# EMG_CHANNEL_2_ANALOG.net
KiCad netlist of a schematic drawn in Altium Designer
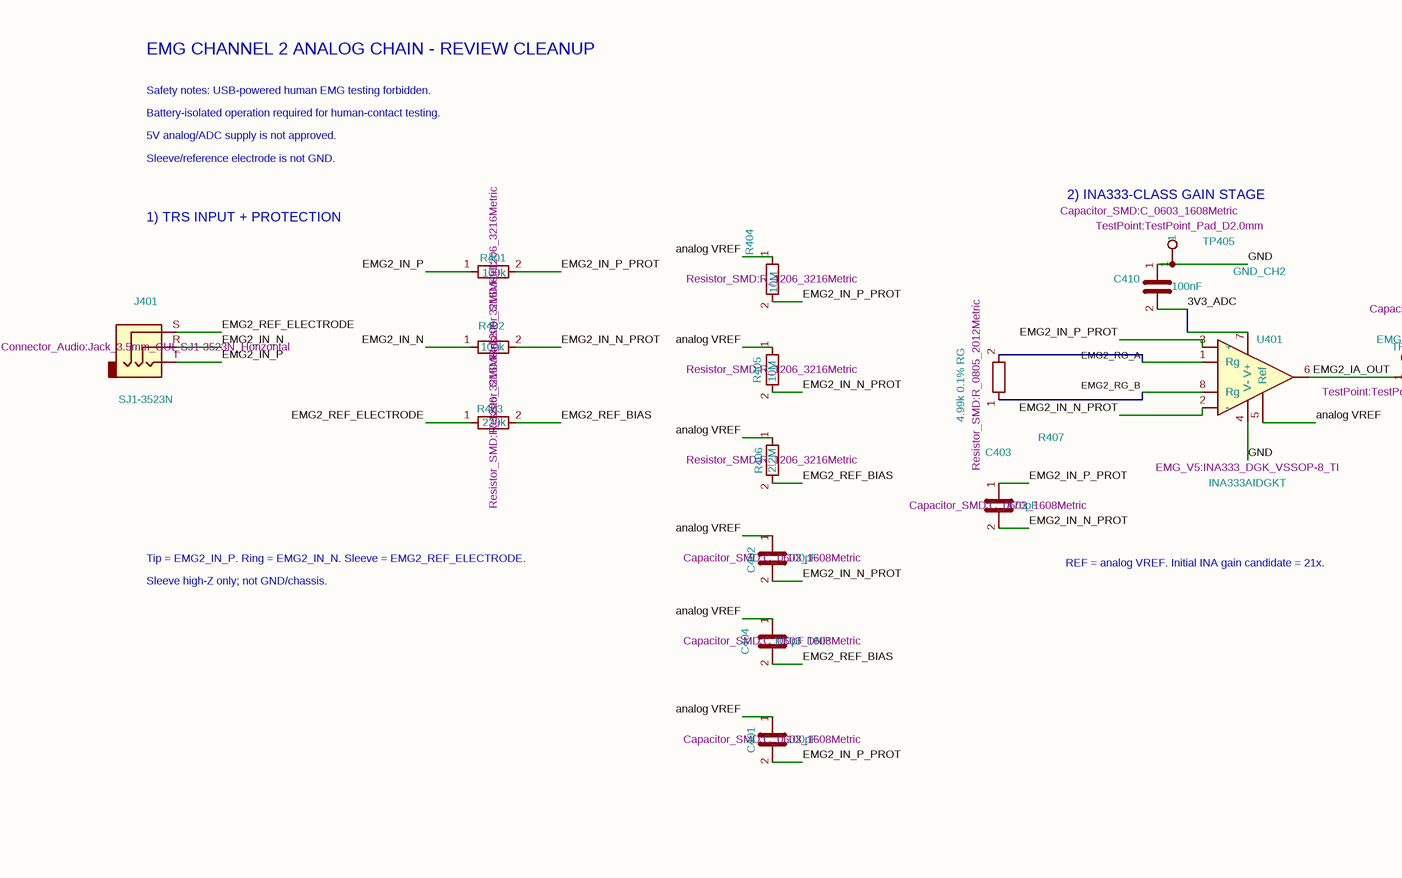
[diagram p0: EMG_CHANNEL_2_ANALOG.SchDoc, left]
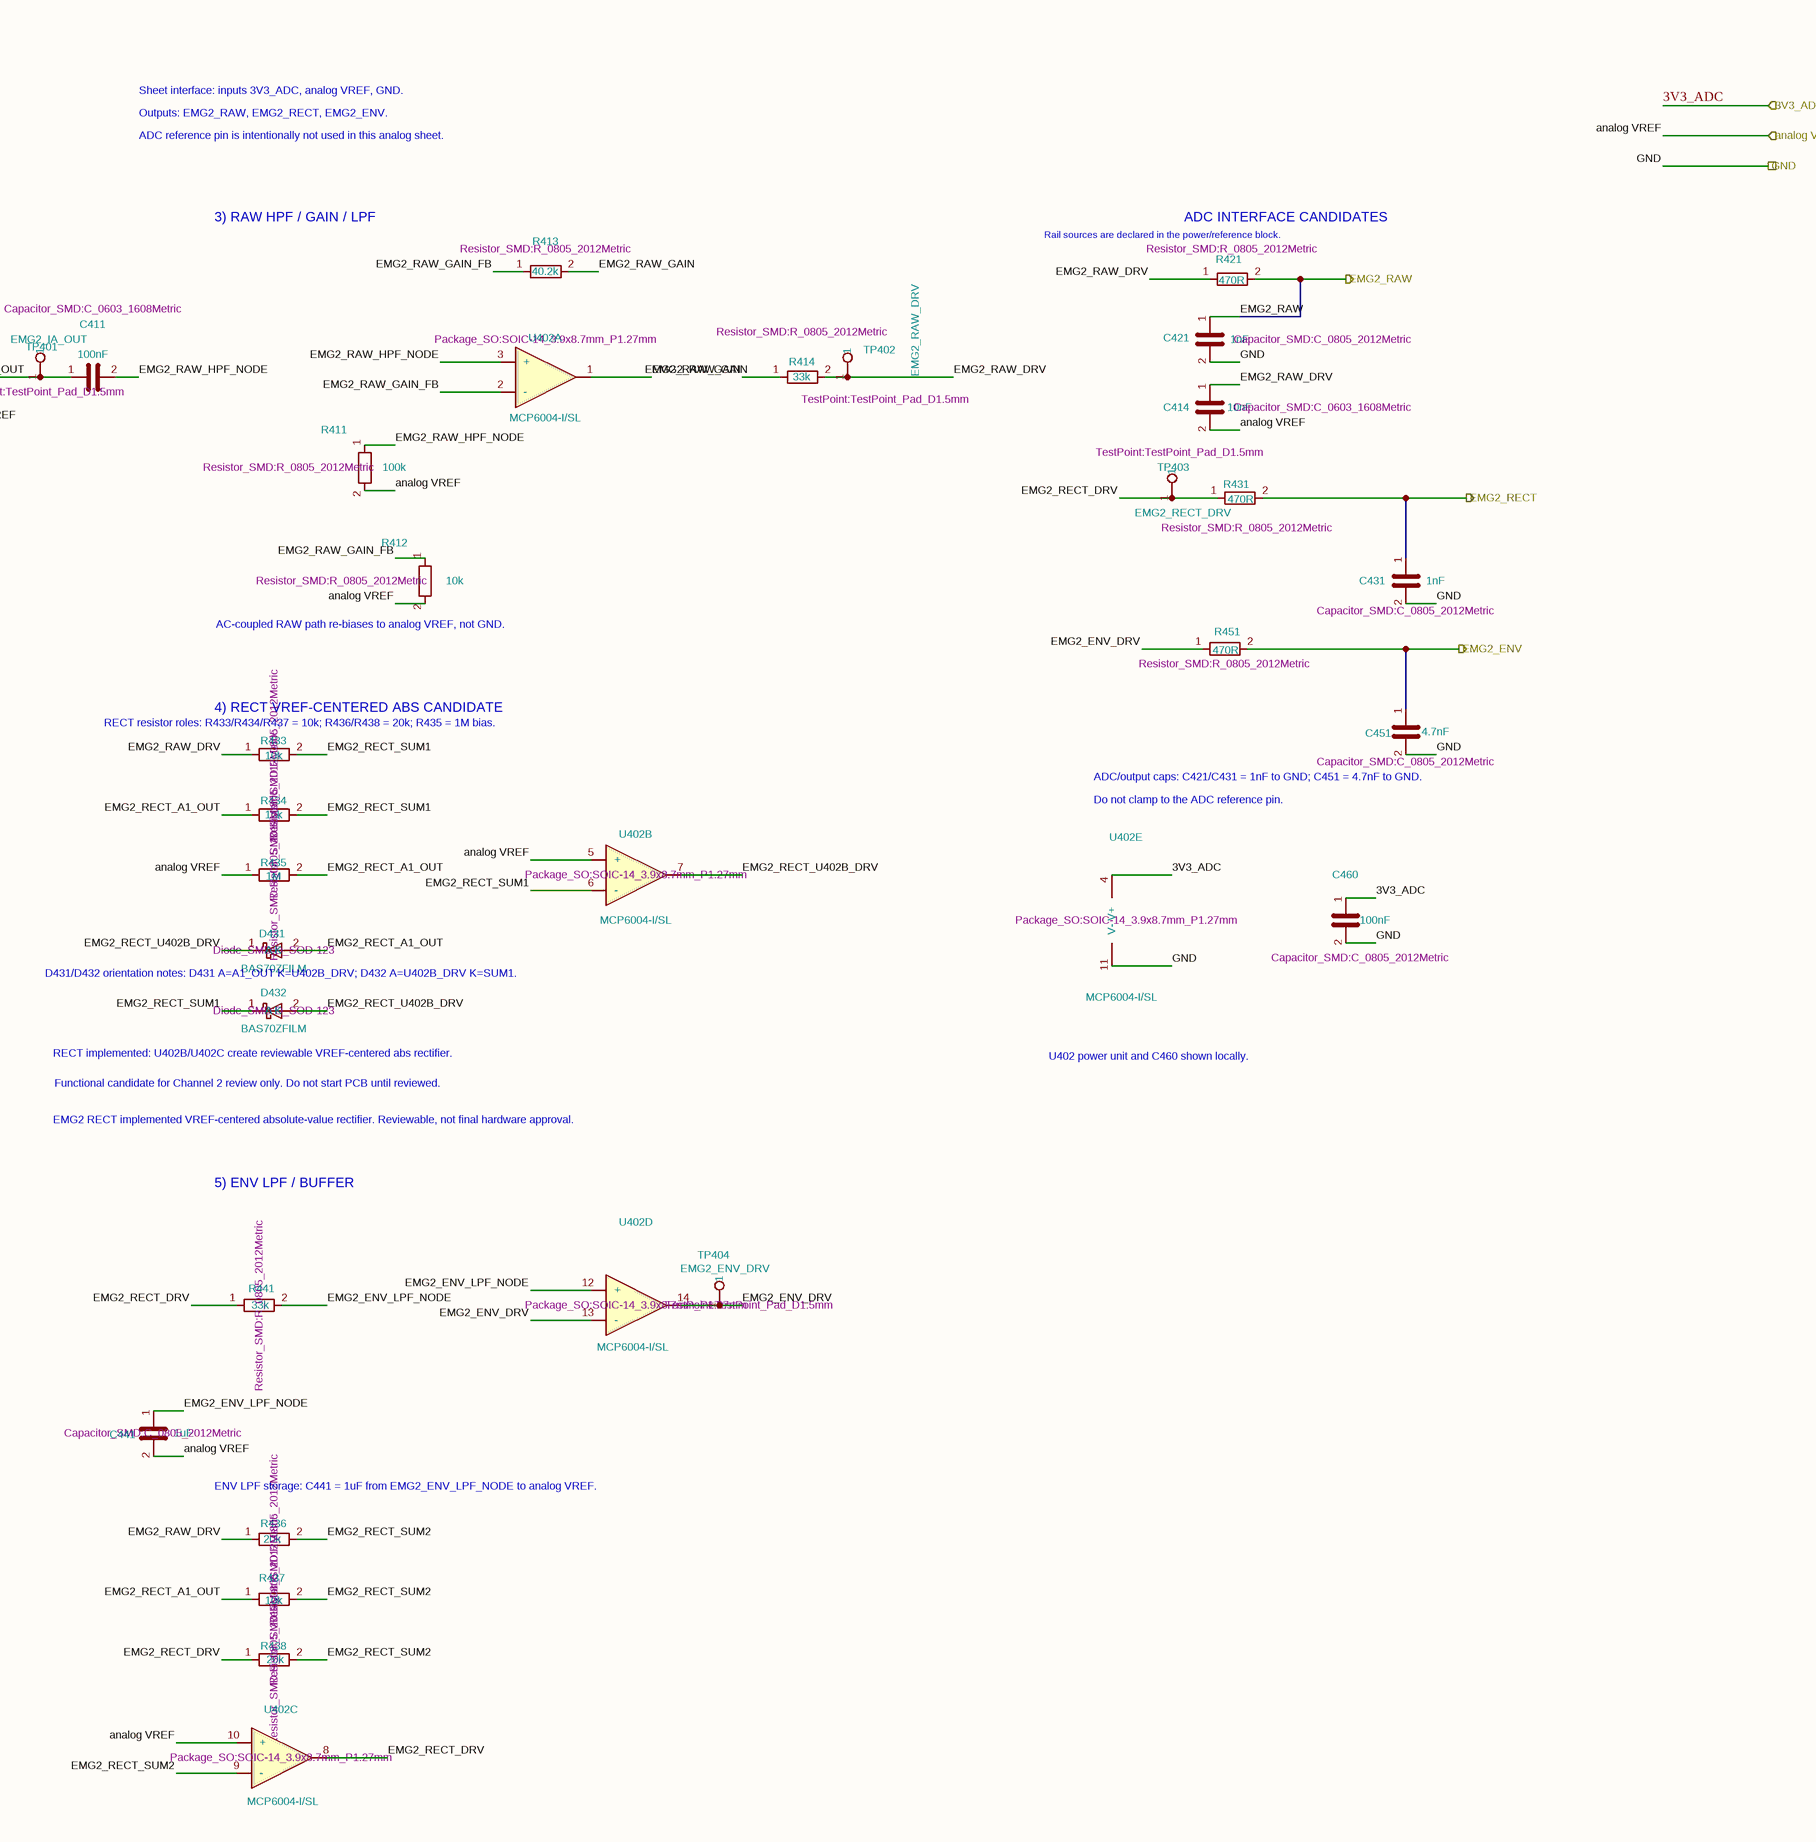
[diagram p1: EMG_CHANNEL_2_ANALOG.SchDoc, right]

(export (version "E")
  (design (tool "Eeschema 10.0.6"))
  (components
    (comp (ref "C401")
      (value "100pF")
      (footprint "Capacitor_SMD:C_0603_1608Metric")
      (libsource (lib "Device") (part "C"))
    )
    (comp (ref "C402")
      (value "100pF")
      (footprint "Capacitor_SMD:C_0603_1608Metric")
      (libsource (lib "Device") (part "C"))
    )
    (comp (ref "C403")
      (value "470pF")
      (footprint "Capacitor_SMD:C_0603_1608Metric")
      (libsource (lib "Device") (part "C"))
    )
    (comp (ref "C404")
      (value "100pF DNP")
      (footprint "Capacitor_SMD:C_0603_1608Metric")
      (libsource (lib "Device") (part "C"))
    )
    (comp (ref "C410")
      (value "100nF")
      (footprint "Capacitor_SMD:C_0603_1608Metric")
      (libsource (lib "Device") (part "C"))
    )
    (comp (ref "C411")
      (value "100nF")
      (footprint "Capacitor_SMD:C_0603_1608Metric")
      (libsource (lib "Device") (part "C"))
    )
    (comp (ref "C414")
      (value "10nF")
      (footprint "Capacitor_SMD:C_0603_1608Metric")
      (libsource (lib "Device") (part "C"))
    )
    (comp (ref "C421")
      (value "1nF")
      (footprint "Capacitor_SMD:C_0805_2012Metric")
      (libsource (lib "Device") (part "C"))
    )
    (comp (ref "C431")
      (value "1nF")
      (footprint "Capacitor_SMD:C_0805_2012Metric")
      (libsource (lib "Device") (part "C"))
    )
    (comp (ref "C441")
      (value "1uF")
      (footprint "Capacitor_SMD:C_0805_2012Metric")
      (libsource (lib "Device") (part "C"))
    )
    (comp (ref "C451")
      (value "4.7nF")
      (footprint "Capacitor_SMD:C_0805_2012Metric")
      (libsource (lib "Device") (part "C"))
    )
    (comp (ref "C460")
      (value "100nF")
      (footprint "Capacitor_SMD:C_0805_2012Metric")
      (libsource (lib "Device") (part "C"))
    )
    (comp (ref "D431")
      (value "BAS70ZFILM")
      (footprint "Diode_SMD:D_SOD-123")
      (libsource (lib "Device") (part "D_Schottky"))
    )
    (comp (ref "D432")
      (value "BAS70ZFILM")
      (footprint "Diode_SMD:D_SOD-123")
      (libsource (lib "Device") (part "D_Schottky"))
    )
    (comp (ref "J401")
      (value "SJ1-3523N")
      (footprint "Connector_Audio:Jack_3.5mm_CUI_SJ1-3523N_Horizontal")
      (libsource (lib "Connector_Audio") (part "AudioJack3"))
    )
    (comp (ref "R401")
      (value "100k")
      (footprint "Resistor_SMD:R_1206_3216Metric")
      (libsource (lib "") (part "R_1"))
    )
    (comp (ref "R402")
      (value "100k")
      (footprint "Resistor_SMD:R_1206_3216Metric")
      (libsource (lib "") (part "R_1"))
    )
    (comp (ref "R403")
      (value "220k")
      (footprint "Resistor_SMD:R_1206_3216Metric")
      (libsource (lib "") (part "R_1"))
    )
    (comp (ref "R404")
      (value "10M")
      (footprint "Resistor_SMD:R_1206_3216Metric")
      (libsource (lib "Device") (part "R"))
    )
    (comp (ref "R405")
      (value "10M")
      (footprint "Resistor_SMD:R_1206_3216Metric")
      (libsource (lib "Device") (part "R"))
    )
    (comp (ref "R406")
      (value "2.2M")
      (footprint "Resistor_SMD:R_1206_3216Metric")
      (libsource (lib "Device") (part "R"))
    )
    (comp (ref "R407")
      (value "4.99k 0.1% RG")
      (footprint "Resistor_SMD:R_0805_2012Metric")
      (libsource (lib "") (part "R_2"))
    )
    (comp (ref "R411")
      (value "100k")
      (footprint "Resistor_SMD:R_0805_2012Metric")
      (libsource (lib "Device") (part "R"))
    )
    (comp (ref "R412")
      (value "10k")
      (footprint "Resistor_SMD:R_0805_2012Metric")
      (libsource (lib "Device") (part "R"))
    )
    (comp (ref "R413")
      (value "40.2k")
      (footprint "Resistor_SMD:R_0805_2012Metric")
      (libsource (lib "") (part "R_1"))
    )
    (comp (ref "R414")
      (value "33k")
      (footprint "Resistor_SMD:R_0805_2012Metric")
      (libsource (lib "") (part "R_1"))
    )
    (comp (ref "R421")
      (value "470R")
      (footprint "Resistor_SMD:R_0805_2012Metric")
      (libsource (lib "") (part "R_1"))
    )
    (comp (ref "R431")
      (value "470R")
      (footprint "Resistor_SMD:R_0805_2012Metric")
      (libsource (lib "") (part "R_1"))
    )
    (comp (ref "R433")
      (value "10k")
      (footprint "Resistor_SMD:R_0805_2012Metric")
      (libsource (lib "") (part "R_1"))
    )
    (comp (ref "R434")
      (value "10k")
      (footprint "Resistor_SMD:R_0805_2012Metric")
      (libsource (lib "") (part "R_1"))
    )
    (comp (ref "R435")
      (value "1M")
      (footprint "Resistor_SMD:R_0805_2012Metric")
      (libsource (lib "") (part "R_1"))
    )
    (comp (ref "R436")
      (value "20k")
      (footprint "Resistor_SMD:R_0805_2012Metric")
      (libsource (lib "") (part "R_1"))
    )
    (comp (ref "R437")
      (value "10k")
      (footprint "Resistor_SMD:R_0805_2012Metric")
      (libsource (lib "") (part "R_1"))
    )
    (comp (ref "R438")
      (value "20k")
      (footprint "Resistor_SMD:R_0805_2012Metric")
      (libsource (lib "") (part "R_1"))
    )
    (comp (ref "R441")
      (value "33k")
      (footprint "Resistor_SMD:R_0805_2012Metric")
      (libsource (lib "") (part "R_1"))
    )
    (comp (ref "R451")
      (value "470R")
      (footprint "Resistor_SMD:R_0805_2012Metric")
      (libsource (lib "") (part "R_1"))
    )
    (comp (ref "TP401")
      (value "EMG2_IA_OUT")
      (footprint "TestPoint:TestPoint_Pad_D1.5mm")
      (libsource (lib "Connector") (part "TestPoint"))
    )
    (comp (ref "TP402")
      (value "EMG2_RAW_DRV")
      (footprint "TestPoint:TestPoint_Pad_D1.5mm")
      (libsource (lib "Connector") (part "TestPoint"))
    )
    (comp (ref "TP403")
      (value "EMG2_RECT_DRV")
      (footprint "TestPoint:TestPoint_Pad_D1.5mm")
      (libsource (lib "Connector") (part "TestPoint"))
    )
    (comp (ref "TP404")
      (value "EMG2_ENV_DRV")
      (footprint "TestPoint:TestPoint_Pad_D1.5mm")
      (libsource (lib "Connector") (part "TestPoint"))
    )
    (comp (ref "TP405")
      (value "GND_CH2")
      (footprint "TestPoint:TestPoint_Pad_D2.0mm")
      (libsource (lib "Connector") (part "TestPoint"))
    )
    (comp (ref "U401")
      (value "INA333AIDGKT")
      (footprint "EMG_V5:INA333_DGK_VSSOP-8_TI")
      (libsource (lib "Amplifier_Instrumentation") (part "INA333xxDGK"))
    )
    (comp (ref "U402")
      (value "MCP6004-I/SL")
      (footprint "Package_SO:SOIC-14_3.9x8.7mm_P1.27mm")
      (libsource (lib "Amplifier_Operational") (part "MCP6004"))
    )
  )
  (nets
    (net (code "1") (name "/3V3_ADC") (class "Default")
      (node (ref "C410") (pin "2") (pinfunction "2_2") (pintype "passive"))
      (node (ref "C460") (pin "1") (pinfunction "1_1") (pintype "passive"))
      (node (ref "U401") (pin "7") (pinfunction "V+_7") (pintype "passive"))
      (node (ref "U402") (pin "4") (pinfunction "V+_4") (pintype "passive"))
    )
    (net (code "2") (name "/EMG2_ENV") (class "Default")
      (node (ref "C451") (pin "1") (pinfunction "1_1") (pintype "passive"))
      (node (ref "R451") (pin "2") (pinfunction "2_2") (pintype "passive"))
    )
    (net (code "3") (name "/EMG2_ENV_DRV") (class "Default")
      (node (ref "R451") (pin "1") (pinfunction "1_1") (pintype "passive"))
      (node (ref "TP404") (pin "1") (pinfunction "1_1") (pintype "passive"))
      (node (ref "U402") (pin "13") (pinfunction "-_13") (pintype "passive"))
      (node (ref "U402") (pin "14") (pinfunction "14_14") (pintype "passive"))
    )
    (net (code "4") (name "/EMG2_ENV_LPF_NODE") (class "Default")
      (node (ref "C441") (pin "1") (pinfunction "1_1") (pintype "passive"))
      (node (ref "R441") (pin "2") (pinfunction "2_2") (pintype "passive"))
      (node (ref "U402") (pin "12") (pinfunction "+_12") (pintype "passive"))
    )
    (net (code "5") (name "/EMG2_IA_OUT") (class "Default")
      (node (ref "C411") (pin "1") (pinfunction "1_1") (pintype "passive"))
      (node (ref "TP401") (pin "1") (pinfunction "1_1") (pintype "passive"))
      (node (ref "U401") (pin "6") (pinfunction "6_6") (pintype "passive"))
    )
    (net (code "6") (name "/EMG2_IN_N") (class "Default")
      (node (ref "J401") (pin "R") (pinfunction "R_R") (pintype "passive"))
      (node (ref "R402") (pin "1") (pinfunction "1_1") (pintype "passive"))
    )
    (net (code "7") (name "/EMG2_IN_N_PROT") (class "Default")
      (node (ref "C402") (pin "2") (pinfunction "2_2") (pintype "passive"))
      (node (ref "C403") (pin "2") (pinfunction "2_2") (pintype "passive"))
      (node (ref "R402") (pin "2") (pinfunction "2_2") (pintype "passive"))
      (node (ref "R405") (pin "2") (pinfunction "2_2") (pintype "passive"))
      (node (ref "U401") (pin "2") (pinfunction "-_2") (pintype "passive"))
    )
    (net (code "8") (name "/EMG2_IN_P") (class "Default")
      (node (ref "J401") (pin "T") (pinfunction "T_T") (pintype "passive"))
      (node (ref "R401") (pin "1") (pinfunction "1_1") (pintype "passive"))
    )
    (net (code "9") (name "/EMG2_IN_P_PROT") (class "Default")
      (node (ref "C401") (pin "2") (pinfunction "2_2") (pintype "passive"))
      (node (ref "C403") (pin "1") (pinfunction "1_1") (pintype "passive"))
      (node (ref "R401") (pin "2") (pinfunction "2_2") (pintype "passive"))
      (node (ref "R404") (pin "2") (pinfunction "2_2") (pintype "passive"))
      (node (ref "U401") (pin "3") (pinfunction "+_3") (pintype "passive"))
    )
    (net (code "10") (name "/EMG2_RAW") (class "Default")
      (node (ref "C421") (pin "1") (pinfunction "1_1") (pintype "passive"))
      (node (ref "R421") (pin "2") (pinfunction "2_2") (pintype "passive"))
    )
    (net (code "11") (name "/EMG2_RAW_DRV") (class "Default")
      (node (ref "C414") (pin "1") (pinfunction "1_1") (pintype "passive"))
      (node (ref "R414") (pin "2") (pinfunction "2_2") (pintype "passive"))
      (node (ref "R421") (pin "1") (pinfunction "1_1") (pintype "passive"))
      (node (ref "R433") (pin "1") (pinfunction "1_1") (pintype "passive"))
      (node (ref "R436") (pin "1") (pinfunction "1_1") (pintype "passive"))
      (node (ref "TP402") (pin "1") (pinfunction "1_1") (pintype "passive"))
    )
    (net (code "12") (name "/EMG2_RAW_GAIN") (class "Default")
      (node (ref "R413") (pin "2") (pinfunction "2_2") (pintype "passive"))
      (node (ref "R414") (pin "1") (pinfunction "1_1") (pintype "passive"))
      (node (ref "U402") (pin "1") (pinfunction "1_1") (pintype "passive"))
    )
    (net (code "13") (name "/EMG2_RAW_GAIN_FB") (class "Default")
      (node (ref "R412") (pin "1") (pinfunction "1_1") (pintype "passive"))
      (node (ref "R413") (pin "1") (pinfunction "1_1") (pintype "passive"))
      (node (ref "U402") (pin "2") (pinfunction "-_2") (pintype "passive"))
    )
    (net (code "14") (name "/EMG2_RAW_HPF_NODE") (class "Default")
      (node (ref "C411") (pin "2") (pinfunction "2_2") (pintype "passive"))
      (node (ref "R411") (pin "1") (pinfunction "1_1") (pintype "passive"))
      (node (ref "U402") (pin "3") (pinfunction "+_3") (pintype "passive"))
    )
    (net (code "15") (name "/EMG2_RECT") (class "Default")
      (node (ref "C431") (pin "1") (pinfunction "1_1") (pintype "passive"))
      (node (ref "R431") (pin "2") (pinfunction "2_2") (pintype "passive"))
    )
    (net (code "16") (name "/EMG2_RECT_A1_OUT") (class "Default")
      (node (ref "D431") (pin "2") (pinfunction "A_2") (pintype "passive"))
      (node (ref "R434") (pin "1") (pinfunction "1_1") (pintype "passive"))
      (node (ref "R435") (pin "2") (pinfunction "2_2") (pintype "passive"))
      (node (ref "R437") (pin "1") (pinfunction "1_1") (pintype "passive"))
    )
    (net (code "17") (name "/EMG2_RECT_DRV") (class "Default")
      (node (ref "R431") (pin "1") (pinfunction "1_1") (pintype "passive"))
      (node (ref "R438") (pin "1") (pinfunction "1_1") (pintype "passive"))
      (node (ref "R441") (pin "1") (pinfunction "1_1") (pintype "passive"))
      (node (ref "TP403") (pin "1") (pinfunction "1_1") (pintype "passive"))
      (node (ref "U402") (pin "8") (pinfunction "8_8") (pintype "passive"))
    )
    (net (code "18") (name "/EMG2_RECT_SUM1") (class "Default")
      (node (ref "D432") (pin "1") (pinfunction "K_1") (pintype "passive"))
      (node (ref "R433") (pin "2") (pinfunction "2_2") (pintype "passive"))
      (node (ref "R434") (pin "2") (pinfunction "2_2") (pintype "passive"))
      (node (ref "U402") (pin "6") (pinfunction "-_6") (pintype "passive"))
    )
    (net (code "19") (name "/EMG2_RECT_SUM2") (class "Default")
      (node (ref "R436") (pin "2") (pinfunction "2_2") (pintype "passive"))
      (node (ref "R437") (pin "2") (pinfunction "2_2") (pintype "passive"))
      (node (ref "R438") (pin "2") (pinfunction "2_2") (pintype "passive"))
      (node (ref "U402") (pin "9") (pinfunction "-_9") (pintype "passive"))
    )
    (net (code "20") (name "/EMG2_RECT_U402B_DRV") (class "Default")
      (node (ref "D431") (pin "1") (pinfunction "K_1") (pintype "passive"))
      (node (ref "D432") (pin "2") (pinfunction "A_2") (pintype "passive"))
      (node (ref "U402") (pin "7") (pinfunction "7_7") (pintype "passive"))
    )
    (net (code "21") (name "/EMG2_REF_BIAS") (class "Default")
      (node (ref "C404") (pin "2") (pinfunction "2_2") (pintype "passive"))
      (node (ref "R403") (pin "2") (pinfunction "2_2") (pintype "passive"))
      (node (ref "R406") (pin "2") (pinfunction "2_2") (pintype "passive"))
    )
    (net (code "22") (name "/EMG2_REF_ELECTRODE") (class "Default")
      (node (ref "J401") (pin "S") (pinfunction "S_S") (pintype "passive"))
      (node (ref "R403") (pin "1") (pinfunction "1_1") (pintype "passive"))
    )
    (net (code "23") (name "/EMG2_RG_A") (class "Default")
      (node (ref "R407") (pin "2") (pinfunction "2_2") (pintype "passive"))
      (node (ref "U401") (pin "1") (pinfunction "Rg_1") (pintype "passive"))
    )
    (net (code "24") (name "/EMG2_RG_B") (class "Default")
      (node (ref "R407") (pin "1") (pinfunction "1_1") (pintype "passive"))
      (node (ref "U401") (pin "8") (pinfunction "Rg_8") (pintype "passive"))
    )
    (net (code "25") (name "/GND") (class "Default")
      (node (ref "C410") (pin "1") (pinfunction "1_1") (pintype "passive"))
      (node (ref "C421") (pin "2") (pinfunction "2_2") (pintype "passive"))
      (node (ref "C431") (pin "2") (pinfunction "2_2") (pintype "passive"))
      (node (ref "C451") (pin "2") (pinfunction "2_2") (pintype "passive"))
      (node (ref "C460") (pin "2") (pinfunction "2_2") (pintype "passive"))
      (node (ref "TP405") (pin "1") (pinfunction "1_1") (pintype "passive"))
      (node (ref "U401") (pin "4") (pinfunction "V-_4") (pintype "passive"))
      (node (ref "U402") (pin "11") (pinfunction "V-_11") (pintype "passive"))
    )
    (net (code "26") (name "/analog VREF") (class "Default")
      (node (ref "C401") (pin "1") (pinfunction "1_1") (pintype "passive"))
      (node (ref "C402") (pin "1") (pinfunction "1_1") (pintype "passive"))
      (node (ref "C404") (pin "1") (pinfunction "1_1") (pintype "passive"))
      (node (ref "C414") (pin "2") (pinfunction "2_2") (pintype "passive"))
      (node (ref "C441") (pin "2") (pinfunction "2_2") (pintype "passive"))
      (node (ref "R404") (pin "1") (pinfunction "1_1") (pintype "passive"))
      (node (ref "R405") (pin "1") (pinfunction "1_1") (pintype "passive"))
      (node (ref "R406") (pin "1") (pinfunction "1_1") (pintype "passive"))
      (node (ref "R411") (pin "2") (pinfunction "2_2") (pintype "passive"))
      (node (ref "R412") (pin "2") (pinfunction "2_2") (pintype "passive"))
      (node (ref "R435") (pin "1") (pinfunction "1_1") (pintype "passive"))
      (node (ref "U401") (pin "5") (pinfunction "Ref_5") (pintype "passive"))
      (node (ref "U402") (pin "10") (pinfunction "+_10") (pintype "passive"))
      (node (ref "U402") (pin "5") (pinfunction "+_5") (pintype "passive"))
    )
  )
)
